# PCB_Hacker_Card_June_2024.net
KiCad netlist of a schematic drawn in EasyEDA
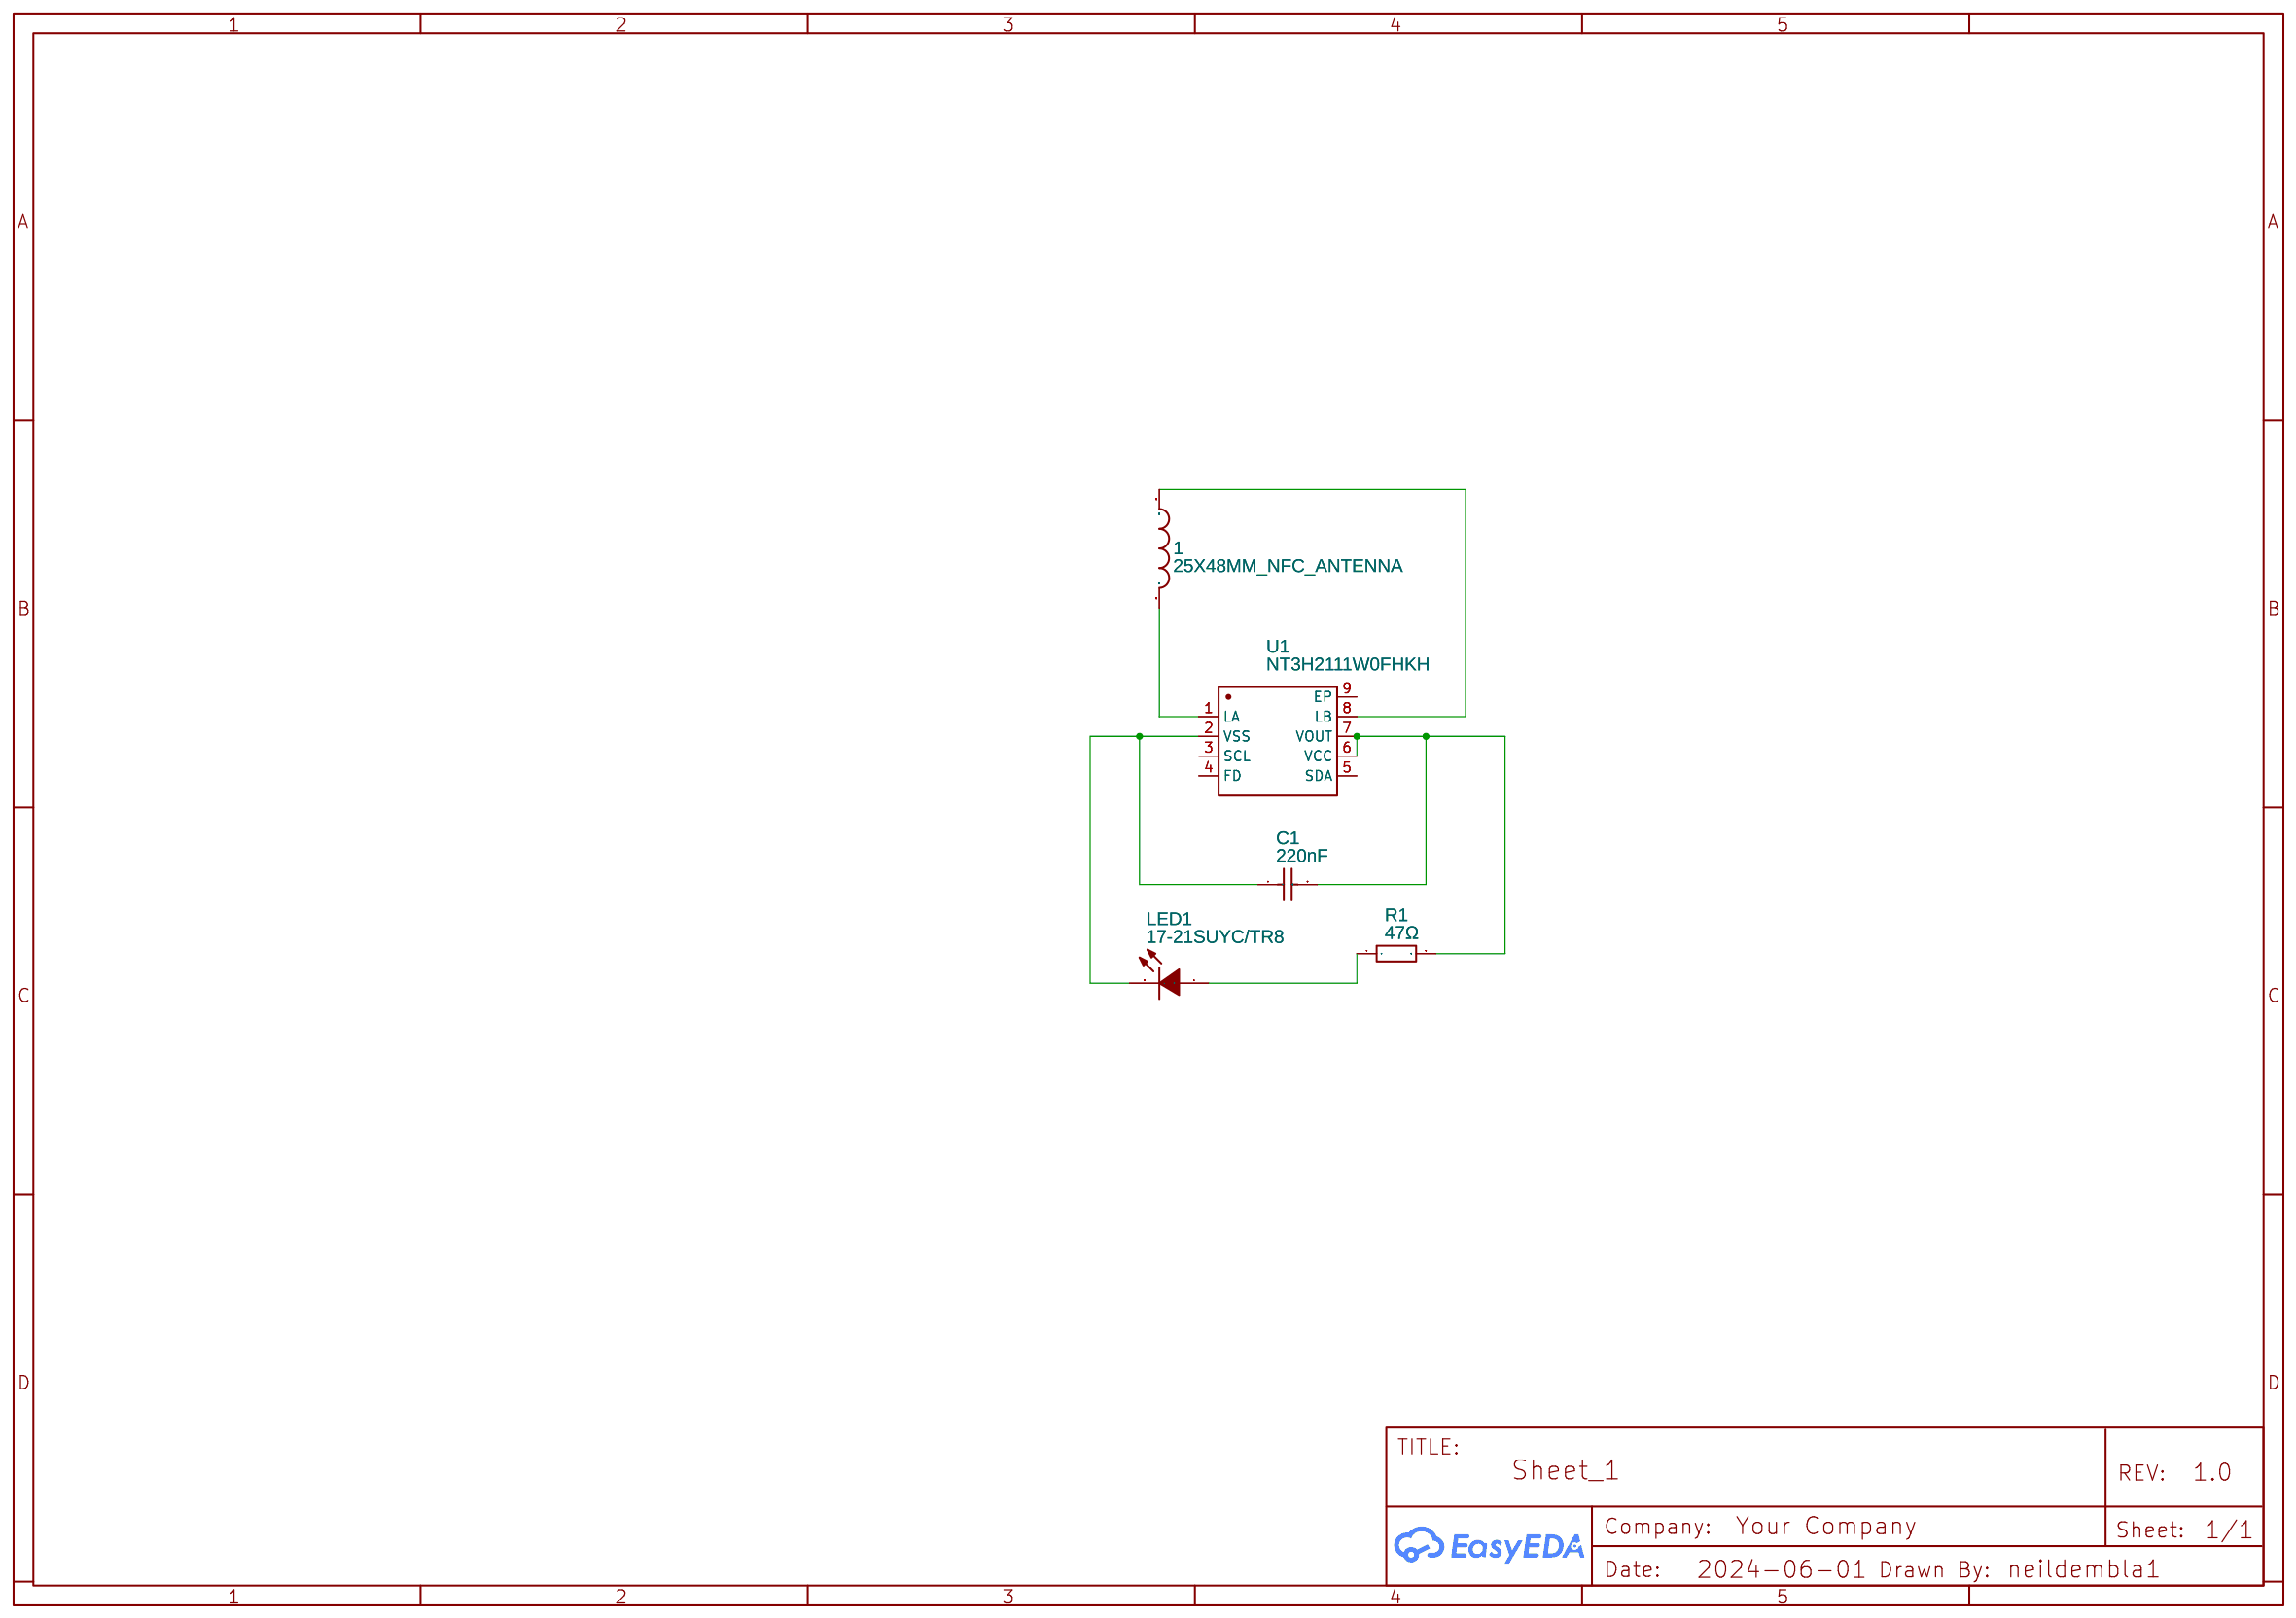
[diagram p0: schematic sheet]

(export (version "E")
  (design (tool "Eeschema 10.0.6"))
  (components
    (comp (ref "1") (value "25X48MM_NFC_ANTENNA") (libsource (lib "") (part "25X48MM_NFC_ANTENNA")))
    (comp (ref "C1")
      (value "220nF")
      (fields
        (field (name "Manufacturer Part") "CL10B224KA8NNNC")
        (field (name "Manufacturer") "SAMSUNG(三星)")
      )
      (libsource (lib "") (part "CL10B224KA8NNNC"))
    )
    (comp (ref "LED1")
      (value "17-21SUYC/TR8")
      (fields (field (name "Manufacturer Part") "KT-0805黄灯") (field (name "Manufacturer") "KENTO"))
      (libsource (lib "") (part "17-21SUYC/TR8"))
    )
    (comp (ref "R1")
      (value "47Ω")
      (fields
        (field (name "Manufacturer Part") "0603WAF470JT5E")
        (field (name "Manufacturer") "UNI-ROYAL(厚声)")
      )
      (libsource (lib "") (part "0603WAF470JT5E"))
    )
    (comp (ref "U1")
      (value "NT3H2111W0FHKH")
      (fields (field (name "Manufacturer") "NXP(恩智浦)"))
      (libsource (lib "") (part "NT3H2111W0FHKH"))
    )
  )
  (nets
    (net (code "1") (name "Net-(LED1-+)") (class "Default")
      (node (ref "LED1") (pin "1") (pinfunction "+_1") (pintype "unspecified"))
      (node (ref "R1") (pin "1") (pinfunction "1_1") (pintype "input"))
    )
    (net (code "2") (name "Net-(LED1--)") (class "Default")
      (node (ref "C1") (pin "1") (pinfunction "1_1") (pintype "input"))
      (node (ref "LED1") (pin "2") (pinfunction "-_2") (pintype "unspecified"))
      (node (ref "U1") (pin "2") (pinfunction "VSS_2") (pintype "unspecified"))
    )
    (net (code "3") (name "Net-(U1-LA)") (class "Default")
      (node (ref "1") (pin "P$2") (pinfunction "P$2_P$2") (pintype "bidirectional"))
      (node (ref "U1") (pin "1") (pinfunction "LA_1") (pintype "unspecified"))
    )
    (net (code "4") (name "Net-(U1-LB)") (class "Default")
      (node (ref "1") (pin "P$1") (pinfunction "P$1_P$1") (pintype "bidirectional"))
      (node (ref "U1") (pin "8") (pinfunction "LB_8") (pintype "unspecified"))
    )
    (net (code "5") (name "Net-(U1-VCC)") (class "Default")
      (node (ref "C1") (pin "2") (pinfunction "2_2") (pintype "input"))
      (node (ref "R1") (pin "2") (pinfunction "2_2") (pintype "input"))
      (node (ref "U1") (pin "6") (pinfunction "VCC_6") (pintype "unspecified"))
      (node (ref "U1") (pin "7") (pinfunction "VOUT_7") (pintype "unspecified"))
    )
    (net (code "6") (name "unconnected-(U1-EP-Pad9)") (class "Default")
      (node (ref "U1") (pin "9") (pinfunction "EP_9") (pintype "unspecified"))
    )
    (net (code "7") (name "unconnected-(U1-FD-Pad4)") (class "Default")
      (node (ref "U1") (pin "4") (pinfunction "FD_4") (pintype "unspecified"))
    )
    (net (code "8") (name "unconnected-(U1-SCL-Pad3)") (class "Default")
      (node (ref "U1") (pin "3") (pinfunction "SCL_3") (pintype "unspecified"))
    )
    (net (code "9") (name "unconnected-(U1-SDA-Pad5)") (class "Default")
      (node (ref "U1") (pin "5") (pinfunction "SDA_5") (pintype "unspecified"))
    )
  )
)
